# ProProject_Magic_wand_2024-09-22.net
KiCad netlist of a schematic drawn in EasyEDA Pro
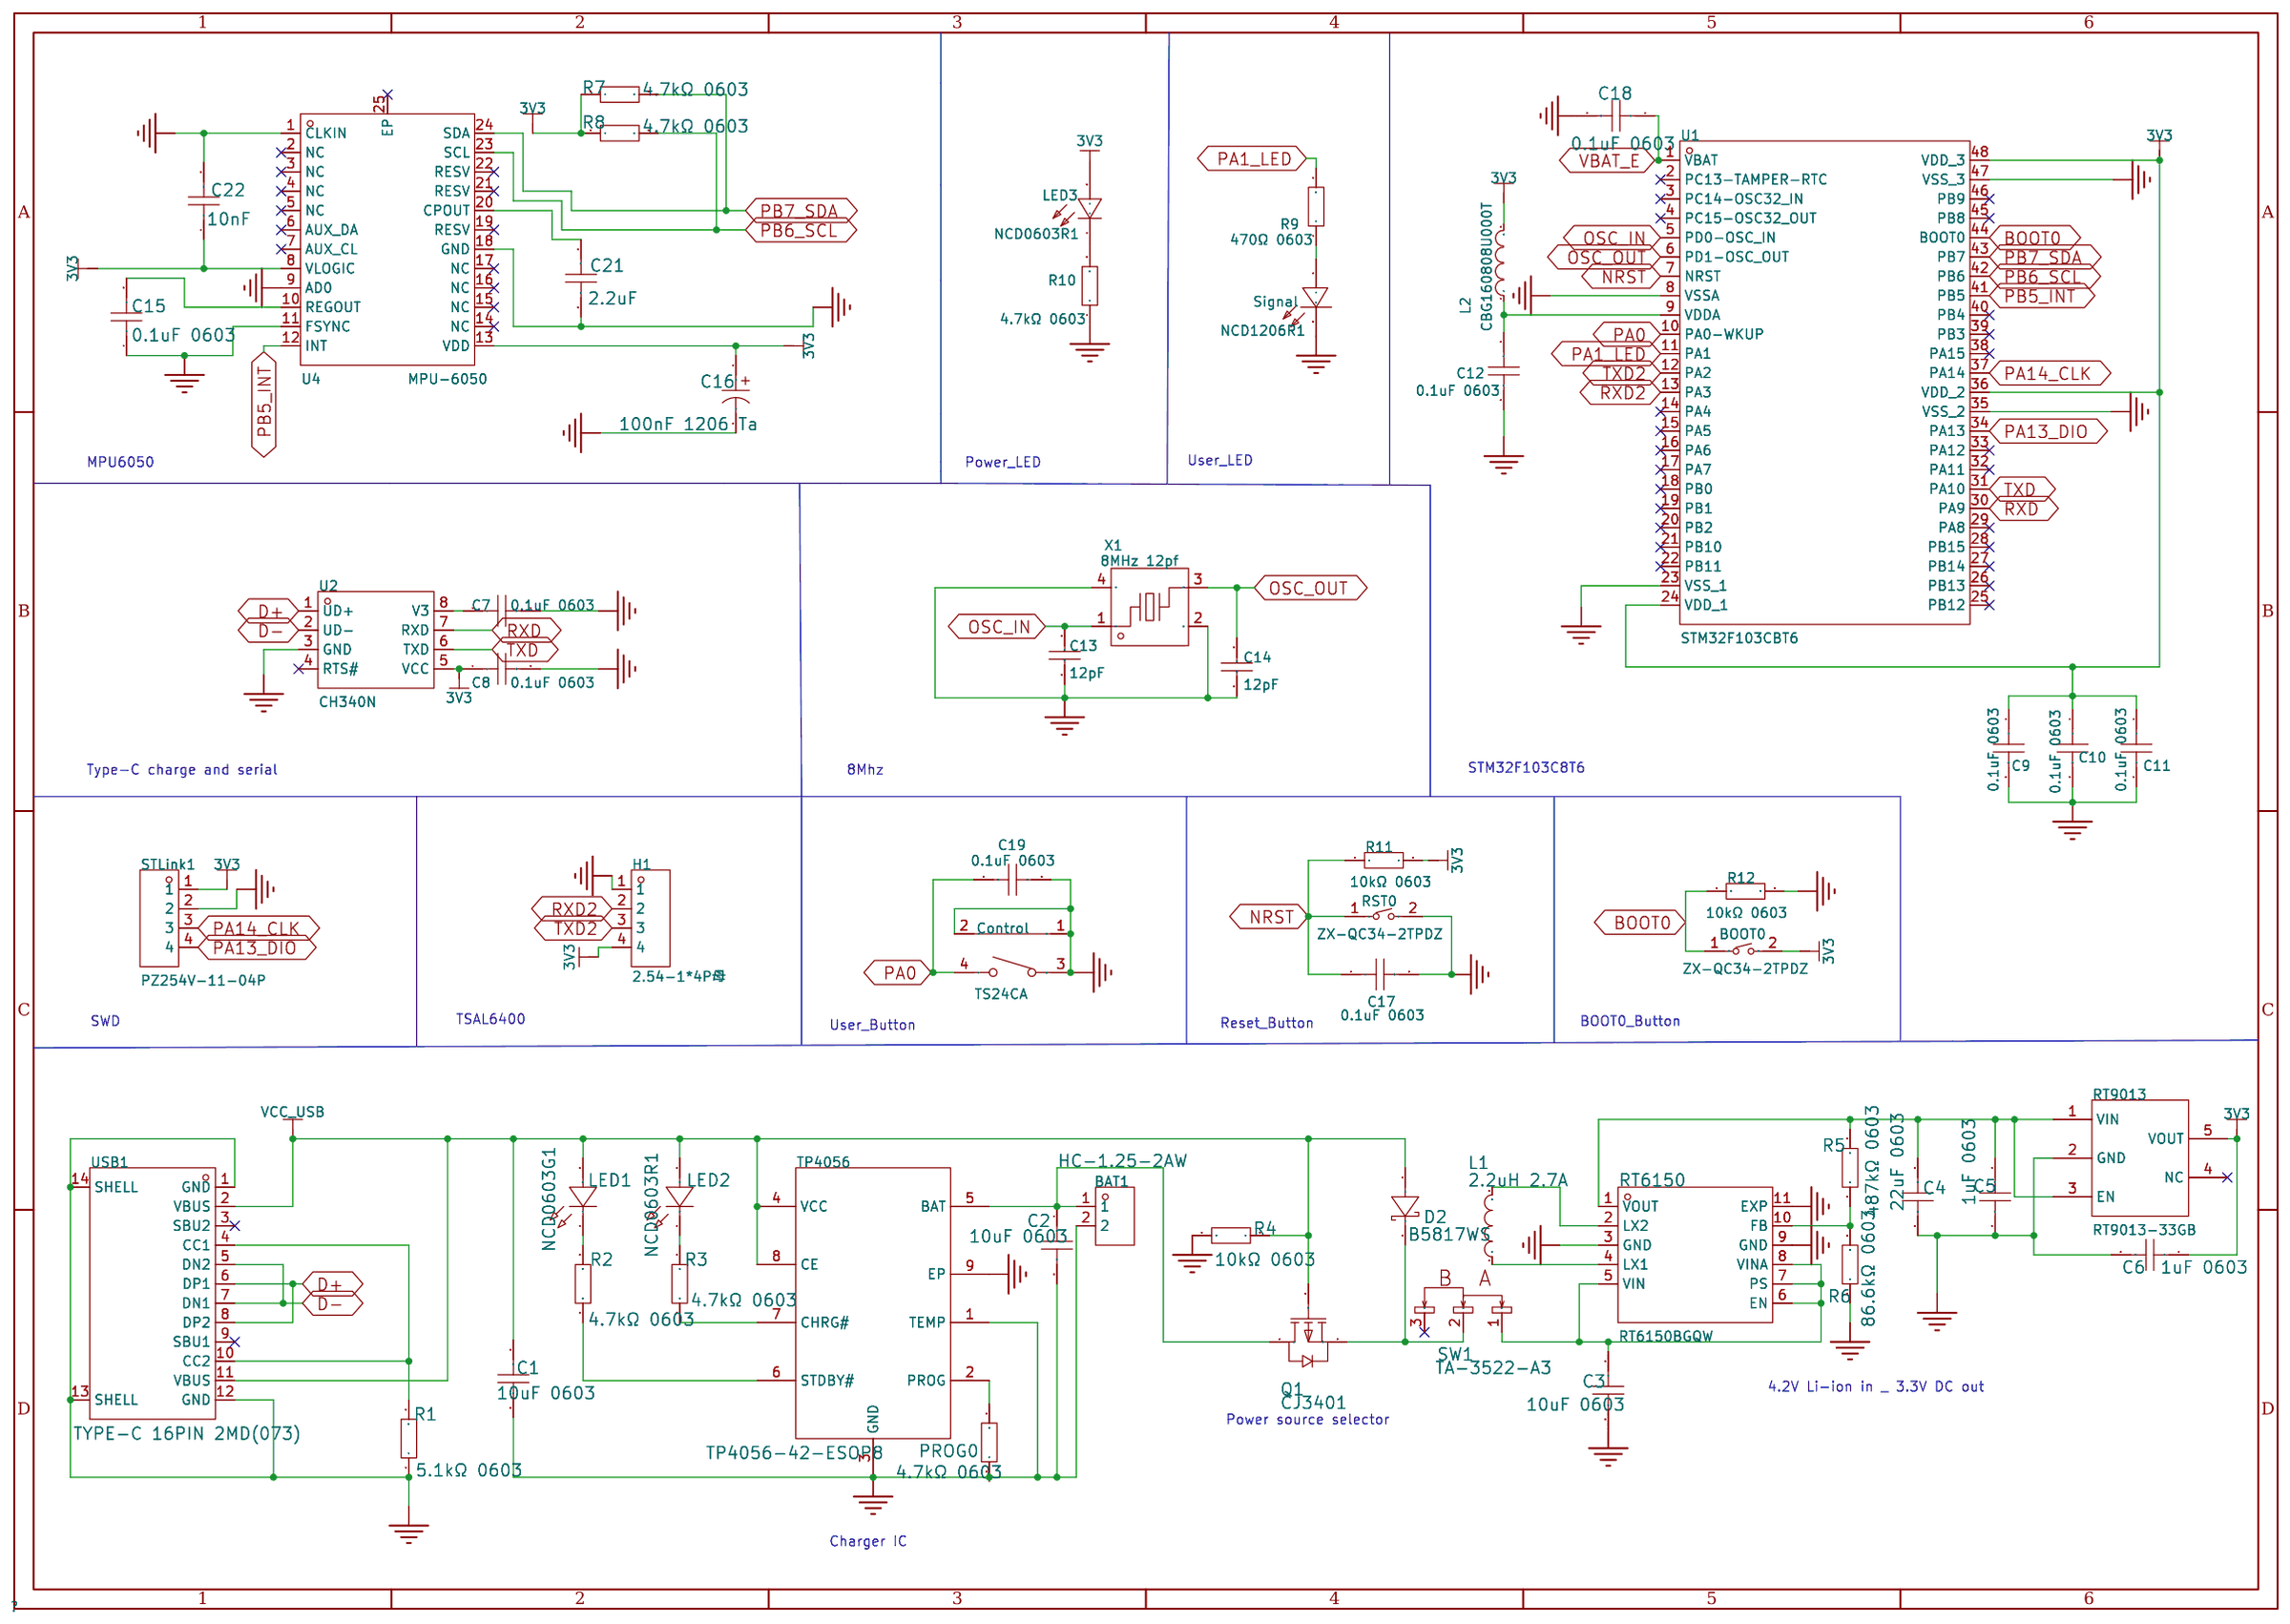
[diagram p0: schematic sheet]

(export (version "E")
  (design (tool "Eeschema 10.0.6"))
  (components
    (comp (ref "BAT1")
      (value "HC-1.25-2AW")
      (footprint "easyedapro:CONN-TH_2P-P1.25_HCTL_HC-1.25-2AW")
      (fields (field (name "Manufacturer") "HCTL(华灿天禄)"))
      (libsource (lib "easyedapro") (part "HC-1.25-2AW"))
    )
    (comp (ref "BOOT0")
      (value "ZX-QC34-2TPDZ")
      (footprint "easyedapro:KEY-SMD_L3.9-W3.0-LS5.0-EH")
      (fields (field (name "Manufacturer") "Megastar(兆星)"))
      (libsource (lib "easyedapro") (part "ZX-QC34-2TPDZ"))
    )
    (comp (ref "C1")
      (value "10uF 0603")
      (footprint "easyedapro:C0603")
      (description "容值:100pF;精度:±5%;额定电压:50V;材质(温度系数):NP0;")
      (fields
        (field (name "Manufacturer Part") "CC0603JRNPO9BN101")
        (field (name "Manufacturer") "YAGEO(国巨)")
      )
      (libsource (lib "easyedapro") (part "CC0603JRNPO9BN101"))
    )
    (comp (ref "C2")
      (value "10uF 0603")
      (footprint "easyedapro:C0603")
      (description "容值:100pF;精度:±5%;额定电压:50V;材质(温度系数):NP0;")
      (fields
        (field (name "Manufacturer Part") "CC0603JRNPO9BN101")
        (field (name "Manufacturer") "YAGEO(国巨)")
      )
      (libsource (lib "easyedapro") (part "CC0603JRNPO9BN101"))
    )
    (comp (ref "C3")
      (value "10uF 0603")
      (footprint "easyedapro:C0603")
      (description "容值:100pF;精度:±5%;额定电压:50V;材质(温度系数):NP0;")
      (fields
        (field (name "Manufacturer Part") "CC0603JRNPO9BN101")
        (field (name "Manufacturer") "YAGEO(国巨)")
      )
      (libsource (lib "easyedapro") (part "CC0603JRNPO9BN101"))
    )
    (comp (ref "C4")
      (value "22uF 0603")
      (footprint "easyedapro:C0603")
      (description "容值:100pF;精度:±5%;额定电压:50V;材质(温度系数):NP0;")
      (fields
        (field (name "Manufacturer Part") "CC0603JRNPO9BN101")
        (field (name "Manufacturer") "YAGEO(国巨)")
      )
      (libsource (lib "easyedapro") (part "CC0603JRNPO9BN101"))
    )
    (comp (ref "C5")
      (value "1uF 0603")
      (footprint "easyedapro:C0603")
      (description "容值:100pF;精度:±5%;额定电压:50V;材质(温度系数):NP0;")
      (fields
        (field (name "Manufacturer Part") "CC0603JRNPO9BN101")
        (field (name "Manufacturer") "YAGEO(国巨)")
      )
      (libsource (lib "easyedapro") (part "CC0603JRNPO9BN101"))
    )
    (comp (ref "C6")
      (value "1uF 0603")
      (footprint "easyedapro:C0603")
      (description "容值:100pF;精度:±5%;额定电压:50V;材质(温度系数):NP0;")
      (fields
        (field (name "Manufacturer Part") "CC0603JRNPO9BN101")
        (field (name "Manufacturer") "YAGEO(国巨)")
      )
      (libsource (lib "easyedapro") (part "CC0603JRNPO9BN101"))
    )
    (comp (ref "C7")
      (value "0.1uF 0603")
      (footprint "easyedapro:C0603")
      (description "容值:100pF;精度:±5%;额定电压:50V;材质(温度系数):NP0;")
      (fields
        (field (name "Manufacturer Part") "CC0603JRNPO9BN101")
        (field (name "Manufacturer") "YAGEO(国巨)")
      )
      (libsource (lib "easyedapro") (part "CC0603JRNPO9BN101"))
    )
    (comp (ref "C8")
      (value "0.1uF 0603")
      (footprint "easyedapro:C0603")
      (description "容值:100pF;精度:±5%;额定电压:50V;材质(温度系数):NP0;")
      (fields
        (field (name "Manufacturer Part") "CC0603JRNPO9BN101")
        (field (name "Manufacturer") "YAGEO(国巨)")
      )
      (libsource (lib "easyedapro") (part "CC0603JRNPO9BN101"))
    )
    (comp (ref "C9")
      (value "0.1uF 0603")
      (footprint "easyedapro:C0603")
      (description "容值:100pF;精度:±5%;额定电压:50V;材质(温度系数):NP0;")
      (fields
        (field (name "Manufacturer Part") "CC0603JRNPO9BN101")
        (field (name "Manufacturer") "YAGEO(国巨)")
      )
      (libsource (lib "easyedapro") (part "CC0603JRNPO9BN101"))
    )
    (comp (ref "C10")
      (value "0.1uF 0603")
      (footprint "easyedapro:C0603")
      (description "容值:100pF;精度:±5%;额定电压:50V;材质(温度系数):NP0;")
      (fields
        (field (name "Manufacturer Part") "CC0603JRNPO9BN101")
        (field (name "Manufacturer") "YAGEO(国巨)")
      )
      (libsource (lib "easyedapro") (part "CC0603JRNPO9BN101"))
    )
    (comp (ref "C11")
      (value "0.1uF 0603")
      (footprint "easyedapro:C0603")
      (description "容值:100pF;精度:±5%;额定电压:50V;材质(温度系数):NP0;")
      (fields
        (field (name "Manufacturer Part") "CC0603JRNPO9BN101")
        (field (name "Manufacturer") "YAGEO(国巨)")
      )
      (libsource (lib "easyedapro") (part "CC0603JRNPO9BN101"))
    )
    (comp (ref "C12")
      (value "0.1uF 0603")
      (footprint "easyedapro:C0603")
      (description "容值:100pF;精度:±5%;额定电压:50V;材质(温度系数):NP0;")
      (fields
        (field (name "Manufacturer Part") "CC0603JRNPO9BN101")
        (field (name "Manufacturer") "YAGEO(国巨)")
      )
      (libsource (lib "easyedapro") (part "CC0603JRNPO9BN101"))
    )
    (comp (ref "C13")
      (value "12pF")
      (footprint "easyedapro:C0603")
      (description "容值:20pF;精度:±5%;额定电压:50V;材质(温度系数):NP0;")
      (fields
        (field (name "Manufacturer Part") "CC0603JRNPO9BN200")
        (field (name "Manufacturer") "YAGEO(国巨)")
      )
      (libsource (lib "easyedapro") (part "CC0603JRNPO9BN200"))
    )
    (comp (ref "C14")
      (value "12pF")
      (footprint "easyedapro:C0603")
      (description "容值:20pF;精度:±5%;额定电压:50V;材质(温度系数):NP0;")
      (fields
        (field (name "Manufacturer Part") "CC0603JRNPO9BN200")
        (field (name "Manufacturer") "YAGEO(国巨)")
      )
      (libsource (lib "easyedapro") (part "CC0603JRNPO9BN200"))
    )
    (comp (ref "C15")
      (value "0.1uF 0603")
      (footprint "easyedapro:C0603")
      (description "容值:100pF;精度:±5%;额定电压:50V;材质(温度系数):NP0;")
      (fields
        (field (name "Manufacturer Part") "CC0603JRNPO9BN101")
        (field (name "Manufacturer") "YAGEO(国巨)")
      )
      (libsource (lib "easyedapro") (part "CC0603JRNPO9BN101"))
    )
    (comp (ref "C16")
      (value "100nF 1206 Ta")
      (footprint "easyedapro:CAP-SMD_L3.2-W1.6-RD")
      (description "容值:100nF;精度:±10%;额定电压:35V;")
      (fields
        (field (name "Manufacturer Part") "CA45-A-35V-0.1UF-K")
        (field (name "Manufacturer") "CEC(振华新云)")
      )
      (libsource (lib "easyedapro") (part "CA45-A-35V-0.1UF-K"))
    )
    (comp (ref "C17")
      (value "0.1uF 0603")
      (footprint "easyedapro:C0603")
      (description "容值:100pF;精度:±5%;额定电压:50V;材质(温度系数):NP0;")
      (fields
        (field (name "Manufacturer Part") "CC0603JRNPO9BN101")
        (field (name "Manufacturer") "YAGEO(国巨)")
      )
      (libsource (lib "easyedapro") (part "CC0603JRNPO9BN101"))
    )
    (comp (ref "C18")
      (value "0.1uF 0603")
      (footprint "easyedapro:C0603")
      (description "容值:100pF;精度:±5%;额定电压:50V;材质(温度系数):NP0;")
      (fields
        (field (name "Manufacturer Part") "CC0603JRNPO9BN101")
        (field (name "Manufacturer") "YAGEO(国巨)")
      )
      (libsource (lib "easyedapro") (part "CC0603JRNPO9BN101"))
    )
    (comp (ref "C19")
      (value "0.1uF 0603")
      (footprint "easyedapro:C0603")
      (description "容值:100pF;精度:±5%;额定电压:50V;材质(温度系数):NP0;")
      (fields
        (field (name "Manufacturer Part") "CC0603JRNPO9BN101")
        (field (name "Manufacturer") "YAGEO(国巨)")
      )
      (libsource (lib "easyedapro") (part "CC0603JRNPO9BN101"))
    )
    (comp (ref "C21")
      (value "2.2uF")
      (footprint "easyedapro:C0603")
      (description "容值:100pF;精度:±5%;额定电压:50V;材质(温度系数):NP0;")
      (fields
        (field (name "Manufacturer Part") "CL10A225KO8NNNC")
        (field (name "Manufacturer") "SAMSUNG(三星)")
      )
      (libsource (lib "easyedapro") (part "CC0603JRNPO9BN101"))
    )
    (comp (ref "C22")
      (value "10nF")
      (footprint "easyedapro:C0603")
      (description "容值:100pF;精度:±5%;额定电压:50V;材质(温度系数):NP0;")
      (fields
        (field (name "Manufacturer Part") "CC0603KRX7R9BB103")
        (field (name "Manufacturer") "YAGEO(国巨)")
      )
      (libsource (lib "easyedapro") (part "CC0603JRNPO9BN101"))
    )
    (comp (ref "Control")
      (value "TS24CA")
      (footprint "easyedapro:SW-SMD_TS24CA")
      (description "电路结构:单刀单掷;按钮形状:矩形按钮;安装方式:卧贴;开关长度:4.55mm;开关宽度:1.8mm;开关高度:3.5mm;触点电流:50mA;额定电压(DC):12V;带灯:-;机械寿命:-;")
      (fields (field (name "Manufacturer") "SHOU HAN(首韩)"))
      (libsource (lib "easyedapro") (part "TS24CA"))
    )
    (comp (ref "D2")
      (value "B5817WS")
      (footprint "easyedapro:SOD-323_L1.7-W1.3-LS2.5-FD")
      (description "二极管配置:独立式;正向压降(Vf):450mV@1.0A;直流反向耐压(Vr):20V;平均整流电流(Io):1A;")
      (fields (field (name "Manufacturer") "宏迦橙"))
      (libsource (lib "easyedapro") (part "B5817WS_C7420329"))
    )
    (comp (ref "H1")
      (value "2.54-1*4P母")
      (footprint "easyedapro:HDR-TH_4P-P2.54-V-F")
      (fields (field (name "Manufacturer") "BOOMELE(博穆精密)"))
      (libsource (lib "easyedapro") (part "2.54-1*4P母"))
    )
    (comp (ref "L1")
      (value "2.2uH 2.7A")
      (footprint "easyedapro:IND-SMD_L2.5-W2.0")
      (description "电感值:2.2uH;精度:±20%;额定电流:2.3A;饱和电流(Isat):2.7A;类型:-;")
      (fields (field (name "Manufacturer Part") "SRN2512-2R2M") (field (name "Manufacturer") "BOURNS"))
      (libsource (lib "easyedapro") (part "SRN2512-2R2M"))
    )
    (comp (ref "L2")
      (value "CBG160808U000T")
      (footprint "easyedapro:L0603")
      (description "标称阻抗@测试频率:0Ω@100MHz;直流电阻(RDC):100mΩ;")
      (fields (field (name "Manufacturer") "FH(风华)"))
      (libsource (lib "easyedapro") (part "CBG160808U000T"))
    )
    (comp (ref "LED1")
      (value "NCD0603G1")
      (fields (field (name "Manufacturer") "国星光电"))
      (libsource (lib "easyedapro") (part "19-219/ghc-yr2t1b5y/3t"))
    )
    (comp (ref "LED2")
      (value "NCD0603R1")
      (fields (field (name "Manufacturer") "国星光电"))
      (libsource (lib "easyedapro") (part "xl-1608surc-06"))
    )
    (comp (ref "LED3")
      (value "NCD0603R1")
      (footprint "easyedapro:LED0603-RD_RED")
      (fields (field (name "Manufacturer") "国星光电"))
      (libsource (lib "easyedapro") (part "FC-DA1608HRK-620D"))
    )
    (comp (ref "PROG0")
      (value "4.7kΩ 0603")
      (footprint "easyedapro:R0603")
      (description "电阻类型:厚膜电阻;阻值:10kΩ;精度:±1%;功率:100mW;最大工作电压:75V;温度系数:±100ppm/°C;")
      (fields
        (field (name "Manufacturer Part") "0603WAF1002T5E")
        (field (name "Manufacturer") "UNI-ROYAL(厚声)")
      )
      (libsource (lib "easyedapro") (part "0603WAF1002T5E"))
    )
    (comp (ref "Q1")
      (value "CJ3401")
      (footprint "easyedapro:SOT-23-3_L2.9-W1.6-P1.90-LS2.8-BR")
      (fields (field (name "Manufacturer") "CJ(江苏长电/长晶)"))
      (libsource (lib "easyedapro") (part "CJ3401"))
    )
    (comp (ref "R1")
      (value "5.1kΩ 0603")
      (footprint "easyedapro:R0603")
      (description "电阻类型:厚膜电阻;阻值:10kΩ;精度:±1%;功率:100mW;最大工作电压:75V;温度系数:±100ppm/°C;")
      (fields
        (field (name "Manufacturer Part") "0603WAF1002T5E")
        (field (name "Manufacturer") "UNI-ROYAL(厚声)")
      )
      (libsource (lib "easyedapro") (part "0603WAF1002T5E"))
    )
    (comp (ref "R2")
      (value "4.7kΩ 0603")
      (footprint "easyedapro:R0603")
      (description "电阻类型:厚膜电阻;阻值:10kΩ;精度:±1%;功率:100mW;最大工作电压:75V;温度系数:±100ppm/°C;")
      (fields
        (field (name "Manufacturer Part") "0603WAF1002T5E")
        (field (name "Manufacturer") "UNI-ROYAL(厚声)")
      )
      (libsource (lib "easyedapro") (part "0603WAF1002T5E"))
    )
    (comp (ref "R3")
      (value "4.7kΩ 0603")
      (footprint "easyedapro:R0603")
      (description "电阻类型:厚膜电阻;阻值:10kΩ;精度:±1%;功率:100mW;最大工作电压:75V;温度系数:±100ppm/°C;")
      (fields
        (field (name "Manufacturer Part") "0603WAF1002T5E")
        (field (name "Manufacturer") "UNI-ROYAL(厚声)")
      )
      (libsource (lib "easyedapro") (part "0603WAF1002T5E"))
    )
    (comp (ref "R4")
      (value "10kΩ 0603")
      (footprint "easyedapro:R0603")
      (description "电阻类型:厚膜电阻;阻值:10kΩ;精度:±1%;功率:100mW;最大工作电压:75V;温度系数:±100ppm/°C;")
      (fields
        (field (name "Manufacturer Part") "0603WAF1002T5E")
        (field (name "Manufacturer") "UNI-ROYAL(厚声)")
      )
      (libsource (lib "easyedapro") (part "0603WAF1002T5E"))
    )
    (comp (ref "R5")
      (value "487kΩ 0603")
      (footprint "easyedapro:R0603")
      (description "电阻类型:厚膜电阻;阻值:10kΩ;精度:±1%;功率:100mW;最大工作电压:75V;温度系数:±100ppm/°C;")
      (fields
        (field (name "Manufacturer Part") "0603WAF1002T5E")
        (field (name "Manufacturer") "UNI-ROYAL(厚声)")
      )
      (libsource (lib "easyedapro") (part "0603WAF1002T5E"))
    )
    (comp (ref "R6")
      (value "86.6kΩ 0603")
      (footprint "easyedapro:R0603")
      (description "电阻类型:厚膜电阻;阻值:10kΩ;精度:±1%;功率:100mW;最大工作电压:75V;温度系数:±100ppm/°C;")
      (fields
        (field (name "Manufacturer Part") "0603WAF1002T5E")
        (field (name "Manufacturer") "UNI-ROYAL(厚声)")
      )
      (libsource (lib "easyedapro") (part "0603WAF1002T5E"))
    )
    (comp (ref "R7")
      (value "4.7kΩ 0603")
      (footprint "easyedapro:R0603")
      (description "电阻类型:厚膜电阻;阻值:10kΩ;精度:±1%;功率:100mW;最大工作电压:75V;温度系数:±100ppm/°C;")
      (fields
        (field (name "Manufacturer Part") "0603WAF1002T5E")
        (field (name "Manufacturer") "UNI-ROYAL(厚声)")
      )
      (libsource (lib "easyedapro") (part "0603WAF1002T5E"))
    )
    (comp (ref "R8")
      (value "4.7kΩ 0603")
      (footprint "easyedapro:R0603")
      (description "电阻类型:厚膜电阻;阻值:10kΩ;精度:±1%;功率:100mW;最大工作电压:75V;温度系数:±100ppm/°C;")
      (fields
        (field (name "Manufacturer Part") "0603WAF1002T5E")
        (field (name "Manufacturer") "UNI-ROYAL(厚声)")
      )
      (libsource (lib "easyedapro") (part "0603WAF1002T5E"))
    )
    (comp (ref "R9")
      (value "470Ω 0603")
      (footprint "easyedapro:R0603")
      (description "电阻类型:厚膜电阻;阻值:10kΩ;精度:±1%;功率:100mW;最大工作电压:75V;温度系数:±100ppm/°C;")
      (fields
        (field (name "Manufacturer Part") "0603WAF1002T5E")
        (field (name "Manufacturer") "UNI-ROYAL(厚声)")
      )
      (libsource (lib "easyedapro") (part "0603WAF1002T5E"))
    )
    (comp (ref "R10")
      (value "4.7kΩ 0603")
      (footprint "easyedapro:R0603")
      (description "电阻类型:厚膜电阻;阻值:10kΩ;精度:±1%;功率:100mW;最大工作电压:75V;温度系数:±100ppm/°C;")
      (fields
        (field (name "Manufacturer Part") "0603WAF1002T5E")
        (field (name "Manufacturer") "UNI-ROYAL(厚声)")
      )
      (libsource (lib "easyedapro") (part "0603WAF1002T5E"))
    )
    (comp (ref "R11")
      (value "10kΩ 0603")
      (footprint "easyedapro:R0603")
      (description "电阻类型:厚膜电阻;阻值:10kΩ;精度:±1%;功率:100mW;最大工作电压:75V;温度系数:±100ppm/°C;")
      (fields
        (field (name "Manufacturer Part") "0603WAF1002T5E")
        (field (name "Manufacturer") "UNI-ROYAL(厚声)")
      )
      (libsource (lib "easyedapro") (part "0603WAF1002T5E"))
    )
    (comp (ref "R12")
      (value "10kΩ 0603")
      (footprint "easyedapro:R0603")
      (description "电阻类型:厚膜电阻;阻值:10kΩ;精度:±1%;功率:100mW;最大工作电压:75V;温度系数:±100ppm/°C;")
      (fields
        (field (name "Manufacturer Part") "0603WAF1002T5E")
        (field (name "Manufacturer") "UNI-ROYAL(厚声)")
      )
      (libsource (lib "easyedapro") (part "0603WAF1002T5E"))
    )
    (comp (ref "RST0")
      (value "ZX-QC34-2TPDZ")
      (footprint "easyedapro:KEY-SMD_L3.9-W3.0-LS5.0-EH")
      (fields (field (name "Manufacturer") "Megastar(兆星)"))
      (libsource (lib "easyedapro") (part "ZX-QC34-2TPDZ"))
    )
    (comp (ref "RT6150")
      (value "RT6150BGQW")
      (footprint "easyedapro:WSON-10_L2.5-W2.5-P0.50-BL-EP")
      (description "功能类型:升降压型;输入电压:1.8V~5.5V;输出电压:1.8V~5.5V;输出电流(最大值):800mA;")
      (fields (field (name "Manufacturer") "RICHTEK(立锜)"))
      (libsource (lib "easyedapro") (part "RT6150BGQW"))
    )
    (comp (ref "RT9013")
      (value "RT9013-33GB")
      (footprint "easyedapro:SOT-23-5_L3.0-W1.7-P0.95-LS2.8-BL")
      (description "输出类型:固定;最大输入电压:5.5V;输出电压:3.3V;最大输出电流:500mA;电源纹波抑制比(PSRR):50dB@(10kHz);输出极性:正极;")
      (fields (field (name "Manufacturer") "RICHTEK(立锜)"))
      (libsource (lib "easyedapro") (part "RT9013-33GB"))
    )
    (comp (ref "Signal")
      (value "NCD1206R1")
      (footprint "easyedapro:LED1206-R-RD_RED")
      (fields (field (name "Manufacturer") "国星光电"))
      (libsource (lib "easyedapro") (part "FC-3215HRK-620D"))
    )
    (comp (ref "STLink1")
      (value "PZ254V-11-04P")
      (footprint "easyedapro:HDR-TH_4P-P2.54-V-M")
      (fields (field (name "Manufacturer") "XFCN(兴飞)"))
      (libsource (lib "easyedapro") (part "PZ254V-11-04P_C2691448"))
    )
    (comp (ref "SW1")
      (value "TA-3522-A3")
      (footprint "easyedapro:SW-TH_3P-L9.1-W3.5-P2.50-A3")
      (fields (field (name "Manufacturer") "Yuandi(元迪)"))
      (libsource (lib "easyedapro") (part "TA-3522-A3"))
    )
    (comp (ref "TP4056")
      (value "TP4056-42-ESOP8")
      (footprint "easyedapro:ESOP-8_L4.9-W3.9-P1.27-LS6.0-BL-EP")
      (description "锂电池充电芯片 42代表电池满电电压4.2V。")
      (fields (field (name "Manufacturer") "TOPPOWER(南京拓微)"))
      (libsource (lib "easyedapro") (part "TP4056"))
    )
    (comp (ref "U1")
      (value "STM32F103CBT6")
      (fields (field (name "Manufacturer") "ST(意法半导体)"))
      (libsource (lib "easyedapro") (part "apm32f103cbt6"))
    )
    (comp (ref "U2")
      (value "CH340N")
      (footprint "easyedapro:SOP-8_L4.9-W3.9-P1.27-LS6.0-BL")
      (fields (field (name "Manufacturer") "WCH(南京沁恒)"))
      (libsource (lib "easyedapro") (part "CH340N_C2977777"))
    )
    (comp (ref "U4")
      (value "MPU-6050")
      (footprint "easyedapro:QFN-24_L4.0-W4.0-P0.50-BL-EP2.7")
      (description "传感器类型:加速度计陀螺仪;")
      (fields (field (name "Manufacturer") "TDK InvenSense(应美盛)"))
      (libsource (lib "easyedapro") (part "MPU-6050_C24112"))
    )
    (comp (ref "USB1")
      (value "TYPE-C 16PIN 2MD(073)")
      (footprint "easyedapro:USB-C-SMD_TYPE-C-6PIN-2MD-073")
      (description "连接器类型:Type-C;标准:-;公母:母;端口数量:1;触点数量:16P;安装方式:卧贴;额定电流 - 电源:5A;工作温度范围:-25°C~+85°C;")
      (fields (field (name "Manufacturer") "SHOU HAN(首韩)"))
      (libsource (lib "easyedapro") (part "TYPE-C 16PIN 2MD(073)"))
    )
    (comp (ref "X1")
      (value "8MHz 12pf")
      (footprint "easyedapro:OSC-SMD_4P-L3.2-W2.5-BL")
      (description "晶振类型:贴片晶振;频率:8MHz;常温频差:±10ppm;外接负载电容:12pF;频率稳定度(全温):±20ppm;")
      (fields (field (name "Manufacturer Part") "X32258MOB4SI") (field (name "Manufacturer") "YXC(扬兴晶振)"))
      (libsource (lib "easyedapro") (part "X32258MOB4SI"))
    )
  )
  (nets
    (net (code "1") (name "3V3") (class "Default")
      (node (ref "BOOT0") (pin "2") (pinfunction "2_2") (pintype "unspecified"))
      (node (ref "C10") (pin "1") (pinfunction "1_1") (pintype "unspecified"))
      (node (ref "C11") (pin "1") (pinfunction "1_1") (pintype "unspecified"))
      (node (ref "C16") (pin "1") (pinfunction "1_1") (pintype "input"))
      (node (ref "C22") (pin "1") (pinfunction "1_1") (pintype "unspecified"))
      (node (ref "C6") (pin "1") (pinfunction "1_1") (pintype "unspecified"))
      (node (ref "C8") (pin "1") (pinfunction "1_1") (pintype "unspecified"))
      (node (ref "C9") (pin "1") (pinfunction "1_1") (pintype "unspecified"))
      (node (ref "H1") (pin "4") (pinfunction "4_4") (pintype "unspecified"))
      (node (ref "L2") (pin "2") (pinfunction "2_2") (pintype "unspecified"))
      (node (ref "LED3") (pin "2") (pinfunction "A_2") (pintype "input"))
      (node (ref "R11") (pin "2") (pinfunction "2_2") (pintype "input"))
      (node (ref "R7") (pin "1") (pinfunction "1_1") (pintype "input"))
      (node (ref "R8") (pin "1") (pinfunction "1_1") (pintype "input"))
      (node (ref "RT9013") (pin "5") (pinfunction "VOUT_5") (pintype "unspecified"))
      (node (ref "STLink1") (pin "1") (pinfunction "1_1") (pintype "unspecified"))
      (node (ref "U1") (pin "24") (pinfunction "VDD_1_24") (pintype "unspecified"))
      (node (ref "U1") (pin "36") (pinfunction "VDD_2_36") (pintype "unspecified"))
      (node (ref "U1") (pin "48") (pinfunction "VDD_3_48") (pintype "unspecified"))
      (node (ref "U2") (pin "5") (pinfunction "VCC_5") (pintype "unspecified"))
      (node (ref "U4") (pin "13") (pinfunction "VDD_13") (pintype "unspecified"))
      (node (ref "U4") (pin "8") (pinfunction "VLOGIC_8") (pintype "unspecified"))
    )
    (net (code "2") (name "BOOT0") (class "Default")
      (node (ref "BOOT0") (pin "1") (pinfunction "1_1") (pintype "unspecified"))
      (node (ref "R12") (pin "1") (pinfunction "1_1") (pintype "input"))
      (node (ref "U1") (pin "44") (pinfunction "BOOT0_44") (pintype "unspecified"))
    )
    (net (code "3") (name "D+") (class "Default")
      (node (ref "U2") (pin "1") (pinfunction "UD+_1") (pintype "unspecified"))
      (node (ref "USB1") (pin "6") (pinfunction "DP1_6") (pintype "unspecified"))
      (node (ref "USB1") (pin "8") (pinfunction "DP2_8") (pintype "unspecified"))
    )
    (net (code "4") (name "D-") (class "Default")
      (node (ref "U2") (pin "2") (pinfunction "UD-_2") (pintype "unspecified"))
      (node (ref "USB1") (pin "5") (pinfunction "DN2_5") (pintype "unspecified"))
      (node (ref "USB1") (pin "7") (pinfunction "DN1_7") (pintype "unspecified"))
    )
    (net (code "5") (name "GND") (class "Default")
      (node (ref "BAT1") (pin "2") (pinfunction "2_2") (pintype "unspecified"))
      (node (ref "C1") (pin "2") (pinfunction "2_2") (pintype "unspecified"))
      (node (ref "C10") (pin "2") (pinfunction "2_2") (pintype "unspecified"))
      (node (ref "C11") (pin "2") (pinfunction "2_2") (pintype "unspecified"))
      (node (ref "C12") (pin "1") (pinfunction "1_1") (pintype "unspecified"))
      (node (ref "C13") (pin "1") (pinfunction "1_1") (pintype "input"))
      (node (ref "C14") (pin "1") (pinfunction "1_1") (pintype "input"))
      (node (ref "C15") (pin "1") (pinfunction "1_1") (pintype "unspecified"))
      (node (ref "C16") (pin "2") (pinfunction "2_2") (pintype "input"))
      (node (ref "C17") (pin "2") (pinfunction "2_2") (pintype "unspecified"))
      (node (ref "C18") (pin "2") (pinfunction "2_2") (pintype "unspecified"))
      (node (ref "C19") (pin "2") (pinfunction "2_2") (pintype "unspecified"))
      (node (ref "C2") (pin "2") (pinfunction "2_2") (pintype "unspecified"))
      (node (ref "C21") (pin "2") (pinfunction "2_2") (pintype "unspecified"))
      (node (ref "C22") (pin "2") (pinfunction "2_2") (pintype "unspecified"))
      (node (ref "C3") (pin "2") (pinfunction "2_2") (pintype "unspecified"))
      (node (ref "C4") (pin "2") (pinfunction "2_2") (pintype "unspecified"))
      (node (ref "C5") (pin "2") (pinfunction "2_2") (pintype "unspecified"))
      (node (ref "C6") (pin "2") (pinfunction "2_2") (pintype "unspecified"))
      (node (ref "C7") (pin "2") (pinfunction "2_2") (pintype "unspecified"))
      (node (ref "C8") (pin "2") (pinfunction "2_2") (pintype "unspecified"))
      (node (ref "C9") (pin "2") (pinfunction "2_2") (pintype "unspecified"))
      (node (ref "Control") (pin "1") (pinfunction "1_1") (pintype "input"))
      (node (ref "Control") (pin "2") (pinfunction "2_2") (pintype "input"))
      (node (ref "Control") (pin "3") (pinfunction "3_3") (pintype "input"))
      (node (ref "H1") (pin "1") (pinfunction "1_1") (pintype "unspecified"))
      (node (ref "PROG0") (pin "1") (pinfunction "1_1") (pintype "input"))
      (node (ref "R1") (pin "1") (pinfunction "1_1") (pintype "input"))
      (node (ref "R10") (pin "1") (pinfunction "1_1") (pintype "input"))
      (node (ref "R12") (pin "2") (pinfunction "2_2") (pintype "input"))
      (node (ref "R4") (pin "2") (pinfunction "2_2") (pintype "input"))
      (node (ref "R6") (pin "1") (pinfunction "1_1") (pintype "input"))
      (node (ref "RST0") (pin "2") (pinfunction "2_2") (pintype "unspecified"))
      (node (ref "RT6150") (pin "11") (pinfunction "EXP_11") (pintype "input"))
      (node (ref "RT6150") (pin "3") (pinfunction "GND_3") (pintype "input"))
      (node (ref "RT6150") (pin "9") (pinfunction "GND_9") (pintype "input"))
      (node (ref "RT9013") (pin "2") (pinfunction "GND_2") (pintype "unspecified"))
      (node (ref "STLink1") (pin "2") (pinfunction "2_2") (pintype "unspecified"))
      (node (ref "Signal") (pin "2") (pinfunction "K_2") (pintype "unspecified"))
      (node (ref "TP4056") (pin "1") (pinfunction "TEMP_1") (pintype "unspecified"))
      (node (ref "TP4056") (pin "3") (pinfunction "GND_3") (pintype "unspecified"))
      (node (ref "TP4056") (pin "9") (pinfunction "EP_9") (pintype "unspecified"))
      (node (ref "U1") (pin "23") (pinfunction "VSS_1_23") (pintype "unspecified"))
      (node (ref "U1") (pin "35") (pinfunction "VSS_2_35") (pintype "unspecified"))
      (node (ref "U1") (pin "47") (pinfunction "VSS_3_47") (pintype "unspecified"))
      (node (ref "U1") (pin "8") (pinfunction "VSSA_8") (pintype "unspecified"))
      (node (ref "U2") (pin "3") (pinfunction "GND_3") (pintype "unspecified"))
      (node (ref "U4") (pin "1") (pinfunction "CLKIN_1") (pintype "unspecified"))
      (node (ref "U4") (pin "11") (pinfunction "FSYNC_11") (pintype "unspecified"))
      (node (ref "U4") (pin "18") (pinfunction "GND_18") (pintype "unspecified"))
      (node (ref "U4") (pin "9") (pinfunction "AD0_9") (pintype "unspecified"))
      (node (ref "USB1") (pin "1") (pinfunction "GND_1") (pintype "unspecified"))
      (node (ref "USB1") (pin "12") (pinfunction "GND_12") (pintype "unspecified"))
      (node (ref "USB1") (pin "13") (pinfunction "SHELL_13") (pintype "unspecified"))
      (node (ref "USB1") (pin "14") (pinfunction "SHELL_14") (pintype "unspecified"))
      (node (ref "X1") (pin "2") (pinfunction "GND_2") (pintype "input"))
      (node (ref "X1") (pin "4") (pinfunction "GND_4") (pintype "input"))
    )
    (net (code "6") (name "NRST") (class "Default")
      (node (ref "C17") (pin "1") (pinfunction "1_1") (pintype "unspecified"))
      (node (ref "R11") (pin "1") (pinfunction "1_1") (pintype "input"))
      (node (ref "RST0") (pin "1") (pinfunction "1_1") (pintype "unspecified"))
      (node (ref "U1") (pin "7") (pinfunction "NRST_7") (pintype "unspecified"))
    )
    (net (code "7") (name "Net-(D2-K)") (class "Default")
      (node (ref "D2") (pin "2") (pinfunction "K_2") (pintype "unspecified"))
      (node (ref "Q1") (pin "2") (pinfunction "S_2") (pintype "unspecified"))
      (node (ref "SW1") (pin "2") (pinfunction "2_2") (pintype "unspecified"))
    )
    (net (code "8") (name "Net-(LED1-K)") (class "Default")
      (node (ref "LED1") (pin "1") (pinfunction "K_1") (pintype "unspecified"))
      (node (ref "R2") (pin "2") (pinfunction "2_2") (pintype "input"))
    )
    (net (code "9") (name "Net-(LED2-K)") (class "Default")
      (node (ref "LED2") (pin "1") (pinfunction "K_1") (pintype "unspecified"))
      (node (ref "R3") (pin "2") (pinfunction "2_2") (pintype "input"))
    )
    (net (code "10") (name "Net-(LED3-K)") (class "Default")
      (node (ref "LED3") (pin "1") (pinfunction "K_1") (pintype "input"))
      (node (ref "R10") (pin "2") (pinfunction "2_2") (pintype "input"))
    )
    (net (code "11") (name "Net-(Q1-D)") (class "Default")
      (node (ref "BAT1") (pin "1") (pinfunction "1_1") (pintype "unspecified"))
      (node (ref "C2") (pin "1") (pinfunction "1_1") (pintype "unspecified"))
      (node (ref "Q1") (pin "3") (pinfunction "D_3") (pintype "unspecified"))
      (node (ref "TP4056") (pin "5") (pinfunction "BAT_5") (pintype "unspecified"))
    )
    (net (code "12") (name "Net-(RT6150-EN)") (class "Default")
      (node (ref "C3") (pin "1") (pinfunction "1_1") (pintype "unspecified"))
      (node (ref "RT6150") (pin "5") (pinfunction "VIN_5") (pintype "input"))
      (node (ref "RT6150") (pin "6") (pinfunction "EN_6") (pintype "input"))
      (node (ref "RT6150") (pin "7") (pinfunction "PS_7") (pintype "input"))
      (node (ref "RT6150") (pin "8") (pinfunction "VINA_8") (pintype "input"))
      (node (ref "SW1") (pin "1") (pinfunction "1_1") (pintype "unspecified"))
    )
    (net (code "13") (name "Net-(RT6150-FB)") (class "Default")
      (node (ref "R5") (pin "1") (pinfunction "1_1") (pintype "input"))
      (node (ref "R6") (pin "2") (pinfunction "2_2") (pintype "input"))
      (node (ref "RT6150") (pin "10") (pinfunction "FB_10") (pintype "input"))
    )
    (net (code "14") (name "Net-(RT6150-LX1)") (class "Default")
      (node (ref "L1") (pin "1") (pinfunction "1_1") (pintype "input"))
      (node (ref "RT6150") (pin "4") (pinfunction "LX1_4") (pintype "input"))
    )
    (net (code "15") (name "Net-(RT6150-LX2)") (class "Default")
      (node (ref "L1") (pin "2") (pinfunction "2_2") (pintype "input"))
      (node (ref "RT6150") (pin "2") (pinfunction "LX2_2") (pintype "input"))
    )
    (net (code "16") (name "Net-(RT6150-VOUT)") (class "Default")
      (node (ref "C4") (pin "1") (pinfunction "1_1") (pintype "unspecified"))
      (node (ref "C5") (pin "1") (pinfunction "1_1") (pintype "unspecified"))
      (node (ref "R5") (pin "2") (pinfunction "2_2") (pintype "input"))
      (node (ref "RT6150") (pin "1") (pinfunction "VOUT_1") (pintype "input"))
      (node (ref "RT9013") (pin "1") (pinfunction "VIN_1") (pintype "unspecified"))
      (node (ref "RT9013") (pin "3") (pinfunction "EN_3") (pintype "unspecified"))
    )
    (net (code "17") (name "Net-(Signal-A)") (class "Default")
      (node (ref "R9") (pin "1") (pinfunction "1_1") (pintype "input"))
      (node (ref "Signal") (pin "1") (pinfunction "A_1") (pintype "unspecified"))
    )
    (net (code "18") (name "Net-(TP4056-CHRG#)") (class "Default")
      (node (ref "R3") (pin "1") (pinfunction "1_1") (pintype "input"))
      (node (ref "TP4056") (pin "7") (pinfunction "CHRG#_7") (pintype "unspecified"))
    )
    (net (code "19") (name "Net-(TP4056-PROG)") (class "Default")
      (node (ref "PROG0") (pin "2") (pinfunction "2_2") (pintype "input"))
      (node (ref "TP4056") (pin "2") (pinfunction "PROG_2") (pintype "unspecified"))
    )
    (net (code "20") (name "Net-(TP4056-STDBY#)") (class "Default")
      (node (ref "R2") (pin "1") (pinfunction "1_1") (pintype "input"))
      (node (ref "TP4056") (pin "6") (pinfunction "STDBY#_6") (pintype "unspecified"))
    )
    (net (code "21") (name "Net-(U1-VDDA)") (class "Default")
      (node (ref "C12") (pin "2") (pinfunction "2_2") (pintype "unspecified"))
      (node (ref "L2") (pin "1") (pinfunction "1_1") (pintype "unspecified"))
      (node (ref "U1") (pin "9") (pinfunction "VDDA_9") (pintype "unspecified"))
    )
    (net (code "22") (name "Net-(U2-V3)") (class "Default")
      (node (ref "C7") (pin "1") (pinfunction "1_1") (pintype "unspecified"))
      (node (ref "U2") (pin "8") (pinfunction "V3_8") (pintype "unspecified"))
    )
    (net (code "23") (name "Net-(U4-CPOUT)") (class "Default")
      (node (ref "C21") (pin "1") (pinfunction "1_1") (pintype "unspecified"))
      (node (ref "U4") (pin "20") (pinfunction "CPOUT_20") (pintype "unspecified"))
    )
    (net (code "24") (name "Net-(U4-REGOUT)") (class "Default")
      (node (ref "C15") (pin "2") (pinfunction "2_2") (pintype "unspecified"))
      (node (ref "U4") (pin "10") (pinfunction "REGOUT_10") (pintype "unspecified"))
    )
    (net (code "25") (name "Net-(USB1-CC1)") (class "Default")
      (node (ref "R1") (pin "2") (pinfunction "2_2") (pintype "input"))
      (node (ref "USB1") (pin "10") (pinfunction "CC2_10") (pintype "unspecified"))
      (node (ref "USB1") (pin "4") (pinfunction "CC1_4") (pintype "unspecified"))
    )
    (net (code "26") (name "OSC_IN") (class "Default")
      (node (ref "C13") (pin "2") (pinfunction "2_2") (pintype "input"))
      (node (ref "U1") (pin "5") (pinfunction "PD0-OSC_IN_5") (pintype "unspecified"))
      (node (ref "X1") (pin "1") (pinfunction "1_1") (pintype "input"))
    )
    (net (code "27") (name "OSC_OUT") (class "Default")
      (node (ref "C14") (pin "2") (pinfunction "2_2") (pintype "input"))
      (node (ref "U1") (pin "6") (pinfunction "PD1-OSC_OUT_6") (pintype "unspecified"))
      (node (ref "X1") (pin "3") (pinfunction "3_3") (pintype "input"))
    )
    (net (code "28") (name "PA0") (class "Default")
      (node (ref "C19") (pin "1") (pinfunction "1_1") (pintype "unspecified"))
      (node (ref "Control") (pin "4") (pinfunction "4_4") (pintype "input"))
      (node (ref "U1") (pin "10") (pinfunction "PA0-WKUP_10") (pintype "unspecified"))
    )
    (net (code "29") (name "PA1_LED") (class "Default")
      (node (ref "R9") (pin "2") (pinfunction "2_2") (pintype "input"))
      (node (ref "U1") (pin "11") (pinfunction "PA1_11") (pintype "unspecified"))
    )
    (net (code "30") (name "PA13_DIO") (class "Default")
      (node (ref "STLink1") (pin "4") (pinfunction "4_4") (pintype "unspecified"))
      (node (ref "U1") (pin "34") (pinfunction "PA13_34") (pintype "unspecified"))
    )
    (net (code "31") (name "PA14_CLK") (class "Default")
      (node (ref "STLink1") (pin "3") (pinfunction "3_3") (pintype "unspecified"))
      (node (ref "U1") (pin "37") (pinfunction "PA14_37") (pintype "unspecified"))
    )
    (net (code "32") (name "PB5_INT") (class "Default")
      (node (ref "U1") (pin "41") (pinfunction "PB5_41") (pintype "unspecified"))
      (node (ref "U4") (pin "12") (pinfunction "INT_12") (pintype "unspecified"))
    )
    (net (code "33") (name "PB6_SCL") (class "Default")
      (node (ref "R8") (pin "2") (pinfunction "2_2") (pintype "input"))
      (node (ref "U1") (pin "42") (pinfunction "PB6_42") (pintype "unspecified"))
      (node (ref "U4") (pin "23") (pinfunction "SCL_23") (pintype "unspecified"))
    )
    (net (code "34") (name "PB7_SDA") (class "Default")
      (node (ref "R7") (pin "2") (pinfunction "2_2") (pintype "input"))
      (node (ref "U1") (pin "43") (pinfunction "PB7_43") (pintype "unspecified"))
      (node (ref "U4") (pin "24") (pinfunction "SDA_24") (pintype "unspecified"))
    )
    (net (code "35") (name "RXD") (class "Default")
      (node (ref "U1") (pin "30") (pinfunction "PA9_30") (pintype "unspecified"))
      (node (ref "U2") (pin "7") (pinfunction "RXD_7") (pintype "unspecified"))
    )
    (net (code "36") (name "RXD2") (class "Default")
      (node (ref "H1") (pin "2") (pinfunction "2_2") (pintype "unspecified"))
      (node (ref "U1") (pin "13") (pinfunction "PA3_13") (pintype "unspecified"))
    )
    (net (code "37") (name "TXD") (class "Default")
      (node (ref "U1") (pin "31") (pinfunction "PA10_31") (pintype "unspecified"))
      (node (ref "U2") (pin "6") (pinfunction "TXD_6") (pintype "unspecified"))
    )
    (net (code "38") (name "TXD2") (class "Default")
      (node (ref "H1") (pin "3") (pinfunction "3_3") (pintype "unspecified"))
      (node (ref "U1") (pin "12") (pinfunction "PA2_12") (pintype "unspecified"))
    )
    (net (code "39") (name "VBAT_E") (class "Default")
      (node (ref "C18") (pin "1") (pinfunction "1_1") (pintype "unspecified"))
      (node (ref "U1") (pin "1") (pinfunction "VBAT_1") (pintype "unspecified"))
    )
    (net (code "40") (name "VCC_USB") (class "Default")
      (node (ref "C1") (pin "1") (pinfunction "1_1") (pintype "unspecified"))
      (node (ref "D2") (pin "1") (pinfunction "A_1") (pintype "unspecified"))
      (node (ref "LED1") (pin "2") (pinfunction "A_2") (pintype "unspecified"))
      (node (ref "LED2") (pin "2") (pinfunction "A_2") (pintype "unspecified"))
      (node (ref "Q1") (pin "1") (pinfunction "G_1") (pintype "unspecified"))
      (node (ref "R4") (pin "1") (pinfunction "1_1") (pintype "input"))
      (node (ref "TP4056") (pin "4") (pinfunction "VCC_4") (pintype "unspecified"))
      (node (ref "TP4056") (pin "8") (pinfunction "CE_8") (pintype "unspecified"))
      (node (ref "USB1") (pin "11") (pinfunction "VBUS_11") (pintype "unspecified"))
      (node (ref "USB1") (pin "2") (pinfunction "VBUS_2") (pintype "unspecified"))
    )
    (net (code "41") (name "unconnected-(RT9013-NC-Pad4)") (class "Default")
      (node (ref "RT9013") (pin "4") (pinfunction "NC_4") (pintype "unspecified+no_connect"))
    )
    (net (code "42") (name "unconnected-(SW1-Pad3)") (class "Default")
      (node (ref "SW1") (pin "3") (pinfunction "3_3") (pintype "unspecified+no_connect"))
    )
    (net (code "43") (name "unconnected-(U1-PA4-Pad14)") (class "Default")
      (node (ref "U1") (pin "14") (pinfunction "PA4_14") (pintype "unspecified+no_connect"))
    )
    (net (code "44") (name "unconnected-(U1-PA5-Pad15)") (class "Default")
      (node (ref "U1") (pin "15") (pinfunction "PA5_15") (pintype "unspecified+no_connect"))
    )
    (net (code "45") (name "unconnected-(U1-PA6-Pad16)") (class "Default")
      (node (ref "U1") (pin "16") (pinfunction "PA6_16") (pintype "unspecified+no_connect"))
    )
    (net (code "46") (name "unconnected-(U1-PA7-Pad17)") (class "Default")
      (node (ref "U1") (pin "17") (pinfunction "PA7_17") (pintype "unspecified+no_connect"))
    )
    (net (code "47") (name "unconnected-(U1-PA8-Pad29)") (class "Default")
      (node (ref "U1") (pin "29") (pinfunction "PA8_29") (pintype "unspecified+no_connect"))
    )
    (net (code "48") (name "unconnected-(U1-PA11-Pad32)") (class "Default")
      (node (ref "U1") (pin "32") (pinfunction "PA11_32") (pintype "unspecified+no_connect"))
    )
    (net (code "49") (name "unconnected-(U1-PA12-Pad33)") (class "Default")
      (node (ref "U1") (pin "33") (pinfunction "PA12_33") (pintype "unspecified+no_connect"))
    )
    (net (code "50") (name "unconnected-(U1-PA15-Pad38)") (class "Default")
      (node (ref "U1") (pin "38") (pinfunction "PA15_38") (pintype "unspecified+no_connect"))
    )
    (net (code "51") (name "unconnected-(U1-PB0-Pad18)") (class "Default")
      (node (ref "U1") (pin "18") (pinfunction "PB0_18") (pintype "unspecified+no_connect"))
    )
    (net (code "52") (name "unconnected-(U1-PB1-Pad19)") (class "Default")
      (node (ref "U1") (pin "19") (pinfunction "PB1_19") (pintype "unspecified+no_connect"))
    )
    (net (code "53") (name "unconnected-(U1-PB2-Pad20)") (class "Default")
      (node (ref "U1") (pin "20") (pinfunction "PB2_20") (pintype "unspecified+no_connect"))
    )
    (net (code "54") (name "unconnected-(U1-PB3-Pad39)") (class "Default")
      (node (ref "U1") (pin "39") (pinfunction "PB3_39") (pintype "unspecified+no_connect"))
    )
    (net (code "55") (name "unconnected-(U1-PB4-Pad40)") (class "Default")
      (node (ref "U1") (pin "40") (pinfunction "PB4_40") (pintype "unspecified+no_connect"))
    )
    (net (code "56") (name "unconnected-(U1-PB8-Pad45)") (class "Default")
      (node (ref "U1") (pin "45") (pinfunction "PB8_45") (pintype "unspecified+no_connect"))
    )
    (net (code "57") (name "unconnected-(U1-PB9-Pad46)") (class "Default")
      (node (ref "U1") (pin "46") (pinfunction "PB9_46") (pintype "unspecified+no_connect"))
    )
    (net (code "58") (name "unconnected-(U1-PB10-Pad21)") (class "Default")
      (node (ref "U1") (pin "21") (pinfunction "PB10_21") (pintype "unspecified+no_connect"))
    )
    (net (code "59") (name "unconnected-(U1-PB11-Pad22)") (class "Default")
      (node (ref "U1") (pin "22") (pinfunction "PB11_22") (pintype "unspecified+no_connect"))
    )
    (net (code "60") (name "unconnected-(U1-PB12-Pad25)") (class "Default")
      (node (ref "U1") (pin "25") (pinfunction "PB12_25") (pintype "unspecified+no_connect"))
    )
    (net (code "61") (name "unconnected-(U1-PB13-Pad26)") (class "Default")
      (node (ref "U1") (pin "26") (pinfunction "PB13_26") (pintype "unspecified+no_connect"))
    )
    (net (code "62") (name "unconnected-(U1-PB14-Pad27)") (class "Default")
      (node (ref "U1") (pin "27") (pinfunction "PB14_27") (pintype "unspecified+no_connect"))
    )
    (net (code "63") (name "unconnected-(U1-PB15-Pad28)") (class "Default")
      (node (ref "U1") (pin "28") (pinfunction "PB15_28") (pintype "unspecified+no_connect"))
    )
    (net (code "64") (name "unconnected-(U1-PC13-TAMPER-RTC-Pad2)") (class "Default")
      (node (ref "U1") (pin "2") (pinfunction "PC13-TAMPER-RTC_2") (pintype "unspecified+no_connect"))
    )
    (net (code "65") (name "unconnected-(U1-PC14-OSC32_IN-Pad3)") (class "Default")
      (node (ref "U1") (pin "3") (pinfunction "PC14-OSC32_IN_3") (pintype "unspecified+no_connect"))
    )
    (net (code "66") (name "unconnected-(U1-PC15-OSC32_OUT-Pad4)") (class "Default")
      (node (ref "U1") (pin "4") (pinfunction "PC15-OSC32_OUT_4") (pintype "unspecified+no_connect"))
    )
    (net (code "67") (name "unconnected-(U2-RTS#-Pad4)") (class "Default")
      (node (ref "U2") (pin "4") (pinfunction "RTS#_4") (pintype "unspecified+no_connect"))
    )
    (net (code "68") (name "unconnected-(U4-AUX_CL-Pad7)") (class "Default")
      (node (ref "U4") (pin "7") (pinfunction "AUX_CL_7") (pintype "unspecified+no_connect"))
    )
    (net (code "69") (name "unconnected-(U4-AUX_DA-Pad6)") (class "Default")
      (node (ref "U4") (pin "6") (pinfunction "AUX_DA_6") (pintype "unspecified+no_connect"))
    )
    (net (code "70") (name "unconnected-(U4-EP-Pad25)") (class "Default")
      (node (ref "U4") (pin "25") (pinfunction "EP_25") (pintype "unspecified+no_connect"))
    )
    (net (code "71") (name "unconnected-(U4-NC-Pad2)") (class "Default")
      (node (ref "U4") (pin "2") (pinfunction "NC_2") (pintype "unspecified+no_connect"))
    )
    (net (code "72") (name "unconnected-(U4-NC-Pad3)") (class "Default")
      (node (ref "U4") (pin "3") (pinfunction "NC_3") (pintype "unspecified+no_connect"))
    )
    (net (code "73") (name "unconnected-(U4-NC-Pad4)") (class "Default")
      (node (ref "U4") (pin "4") (pinfunction "NC_4") (pintype "unspecified+no_connect"))
    )
    (net (code "74") (name "unconnected-(U4-NC-Pad5)") (class "Default")
      (node (ref "U4") (pin "5") (pinfunction "NC_5") (pintype "unspecified+no_connect"))
    )
    (net (code "75") (name "unconnected-(U4-NC-Pad14)") (class "Default")
      (node (ref "U4") (pin "14") (pinfunction "NC_14") (pintype "unspecified+no_connect"))
    )
    (net (code "76") (name "unconnected-(U4-NC-Pad15)") (class "Default")
      (node (ref "U4") (pin "15") (pinfunction "NC_15") (pintype "unspecified+no_connect"))
    )
    (net (code "77") (name "unconnected-(U4-NC-Pad16)") (class "Default")
      (node (ref "U4") (pin "16") (pinfunction "NC_16") (pintype "unspecified+no_connect"))
    )
    (net (code "78") (name "unconnected-(U4-NC-Pad17)") (class "Default")
      (node (ref "U4") (pin "17") (pinfunction "NC_17") (pintype "unspecified+no_connect"))
    )
    (net (code "79") (name "unconnected-(U4-RESV-Pad19)") (class "Default")
      (node (ref "U4") (pin "19") (pinfunction "RESV_19") (pintype "unspecified+no_connect"))
    )
    (net (code "80") (name "unconnected-(U4-RESV-Pad21)") (class "Default")
      (node (ref "U4") (pin "21") (pinfunction "RESV_21") (pintype "unspecified+no_connect"))
    )
    (net (code "81") (name "unconnected-(U4-RESV-Pad22)") (class "Default")
      (node (ref "U4") (pin "22") (pinfunction "RESV_22") (pintype "unspecified+no_connect"))
    )
    (net (code "82") (name "unconnected-(USB1-SBU1-Pad9)") (class "Default")
      (node (ref "USB1") (pin "9") (pinfunction "SBU1_9") (pintype "unspecified+no_connect"))
    )
    (net (code "83") (name "unconnected-(USB1-SBU2-Pad3)") (class "Default")
      (node (ref "USB1") (pin "3") (pinfunction "SBU2_3") (pintype "unspecified+no_connect"))
    )
  )
)
